# SAMD21_Pro_RF.net
KiCad netlist of a schematic drawn in EAGLE
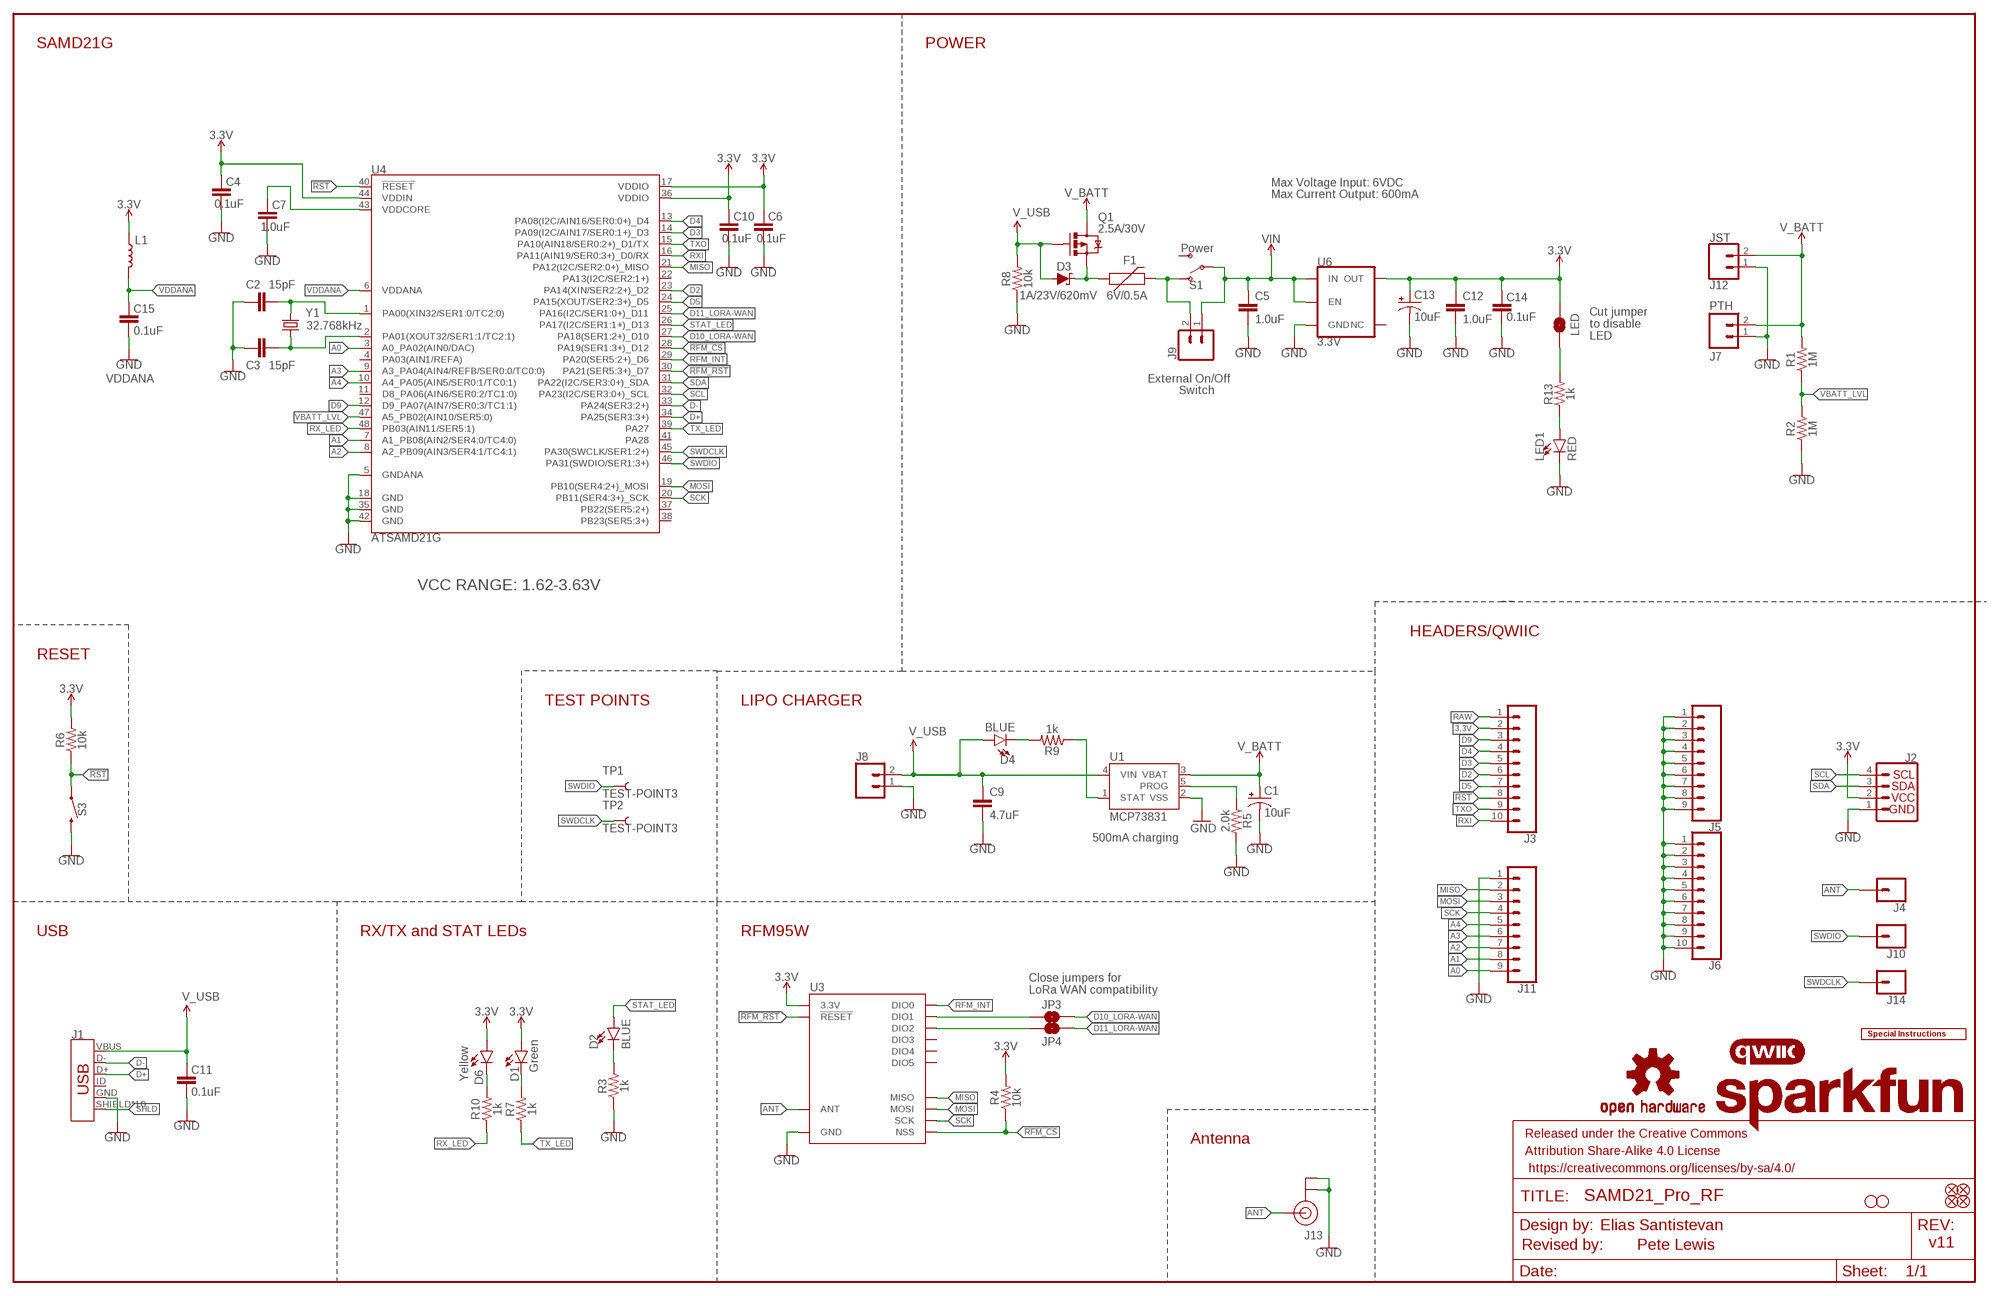
[diagram p0: schematic, sheet 1]

(export (version "E")
  (design (tool "Eeschema 10.0.6"))
  (components
    (comp (ref "C1")
      (value "10uF")
      (footprint "eagle-import:EIA3216")
      (libsource (lib "eagle-import") (part "10UF-POLAR-EIA3216-16V-10%(TANT)"))
    )
    (comp (ref "C2")
      (value "15pF")
      (footprint "eagle-import:0603")
      (libsource (lib "eagle-import") (part "15PF-0603-50V-5%"))
    )
    (comp (ref "C3")
      (value "15pF")
      (footprint "eagle-import:0603")
      (libsource (lib "eagle-import") (part "15PF-0603-50V-5%"))
    )
    (comp (ref "C4")
      (value "0.1uF")
      (footprint "eagle-import:0603")
      (libsource (lib "eagle-import") (part "0.1UF-0603-25V-(+80/-20%)"))
    )
    (comp (ref "C5")
      (value "1.0uF")
      (footprint "eagle-import:0603")
      (libsource (lib "eagle-import") (part "1.0UF-0603-16V-10%"))
    )
    (comp (ref "C6")
      (value "0.1uF")
      (footprint "eagle-import:0603")
      (libsource (lib "eagle-import") (part "0.1UF-0603-25V-(+80/-20%)"))
    )
    (comp (ref "C7")
      (value "1.0uF")
      (footprint "eagle-import:0603")
      (libsource (lib "eagle-import") (part "1.0UF-0603-16V-10%"))
    )
    (comp (ref "C9")
      (value "4.7uF")
      (footprint "eagle-import:0603")
      (libsource (lib "eagle-import") (part "4.7UF-0603-6.3V-(10%)"))
    )
    (comp (ref "C10")
      (value "0.1uF")
      (footprint "eagle-import:0603")
      (libsource (lib "eagle-import") (part "0.1UF-0603-25V-(+80/-20%)"))
    )
    (comp (ref "C11")
      (value "0.1uF")
      (footprint "eagle-import:0603")
      (libsource (lib "eagle-import") (part "0.1UF-0603-25V-(+80/-20%)"))
    )
    (comp (ref "C12")
      (value "1.0uF")
      (footprint "eagle-import:0603")
      (libsource (lib "eagle-import") (part "1.0UF-0603-16V-10%"))
    )
    (comp (ref "C13")
      (value "10uF")
      (footprint "eagle-import:EIA3216")
      (libsource (lib "eagle-import") (part "10UF-POLAR-EIA3216-16V-10%(TANT)"))
    )
    (comp (ref "C14")
      (value "0.1uF")
      (footprint "eagle-import:0603")
      (libsource (lib "eagle-import") (part "0.1UF-0603-25V-(+80/-20%)"))
    )
    (comp (ref "C15")
      (value "0.1uF")
      (footprint "eagle-import:0603")
      (libsource (lib "eagle-import") (part "0.1UF-0603-25V-(+80/-20%)"))
    )
    (comp (ref "D1")
      (value "Green")
      (footprint "eagle-import:LED-0603")
      (libsource (lib "eagle-import") (part "LED-GREEN0603"))
    )
    (comp (ref "D2")
      (value "BLUE")
      (footprint "eagle-import:LED-0603")
      (libsource (lib "eagle-import") (part "LED-BLUE0603"))
    )
    (comp (ref "D3")
      (value "1A/23V/620mV")
      (footprint "eagle-import:SOD-323")
      (libsource (lib "eagle-import") (part "DIODE-SCHOTTKY-BAT20J"))
    )
    (comp (ref "D4")
      (value "BLUE")
      (footprint "eagle-import:LED-0603")
      (libsource (lib "eagle-import") (part "LED-BLUE0603"))
    )
    (comp (ref "D6")
      (value "Yellow")
      (footprint "eagle-import:LED-0603")
      (libsource (lib "eagle-import") (part "LED-YELLOW0603"))
    )
    (comp (ref "F1")
      (value "6V/0.5A")
      (footprint "eagle-import:1206")
      (libsource (lib "eagle-import") (part "PPTC_HALF-AMP"))
    )
    (comp (ref "FD1")
      (value "FIDUCIAL1X2")
      (footprint "eagle-import:FIDUCIAL-1X2")
      (libsource (lib "eagle-import") (part "FIDUCIAL1X2"))
    )
    (comp (ref "FD2")
      (value "FIDUCIAL1X2")
      (footprint "eagle-import:FIDUCIAL-1X2")
      (libsource (lib "eagle-import") (part "FIDUCIAL1X2"))
    )
    (comp (ref "FD3")
      (value "FIDUCIAL1X2")
      (footprint "eagle-import:FIDUCIAL-1X2")
      (libsource (lib "eagle-import") (part "FIDUCIAL1X2"))
    )
    (comp (ref "FD4")
      (value "FIDUCIAL1X2")
      (footprint "eagle-import:FIDUCIAL-1X2")
      (libsource (lib "eagle-import") (part "FIDUCIAL1X2"))
    )
    (comp (ref "FRAME2")
      (value "FRAME-LEDGER")
      (footprint "eagle-import:CREATIVE_COMMONS")
      (libsource (lib "eagle-import") (part "FRAME-LEDGER"))
    )
    (comp (ref "H1")
      (value "STAND-OFFTIGHT")
      (footprint "eagle-import:STAND-OFF-TIGHT")
      (libsource (lib "eagle-import") (part "STAND-OFFTIGHT"))
    )
    (comp (ref "H2")
      (value "STAND-OFFTIGHT")
      (footprint "eagle-import:STAND-OFF-TIGHT")
      (libsource (lib "eagle-import") (part "STAND-OFFTIGHT"))
    )
    (comp (ref "J1")
      (value "USB_MICRO-B_HALF_PTH_MILL")
      (footprint "eagle-import:USB-MICROB-PTH-MILL")
      (libsource (lib "eagle-import") (part "USB_MICRO-B_HALF_PTH_MILL"))
    )
    (comp (ref "J2")
      (value "QWIIC_CONNECTORJS-1MM")
      (footprint "eagle-import:1X04_1MM_RA")
      (libsource (lib "eagle-import") (part "QWIIC_CONNECTORJS-1MM"))
    )
    (comp (ref "J3")
      (value "CONN_10NO_SILK_PTH_FEMALE")
      (footprint "eagle-import:1X10_NO_SILK")
      (libsource (lib "eagle-import") (part "CONN_10NO_SILK_PTH_FEMALE"))
    )
    (comp (ref "J4")
      (value "CONN_01PTH_NO_SILK_YES_STOP")
      (footprint "eagle-import:1X01_NO_SILK")
      (libsource (lib "eagle-import") (part "CONN_01PTH_NO_SILK_YES_STOP"))
    )
    (comp (ref "J5")
      (value "CONN_09NO_SILK")
      (footprint "eagle-import:1X09_NO_SILK")
      (libsource (lib "eagle-import") (part "CONN_09NO_SILK"))
    )
    (comp (ref "J6")
      (value "CONN_10NO_SILK_PTH_FEMALE")
      (footprint "eagle-import:1X10_NO_SILK")
      (libsource (lib "eagle-import") (part "CONN_10NO_SILK_PTH_FEMALE"))
    )
    (comp (ref "J7")
      (value "PTH")
      (footprint "eagle-import:1X02_NO_SILK")
      (libsource (lib "eagle-import") (part "CONN_021X02_NO_SILK"))
    )
    (comp (ref "J8")
      (value "CONN_021X02_NO_SILK")
      (footprint "eagle-import:1X02_NO_SILK")
      (libsource (lib "eagle-import") (part "CONN_021X02_NO_SILK"))
    )
    (comp (ref "J9")
      (value "External On/Off")
      (footprint "eagle-import:1X02_NO_SILK")
      (libsource (lib "eagle-import") (part "CONN_021X02_NO_SILK"))
    )
    (comp (ref "J10")
      (value "CONN_01PTH_NO_SILK_YES_STOP")
      (footprint "eagle-import:1X01_NO_SILK")
      (libsource (lib "eagle-import") (part "CONN_01PTH_NO_SILK_YES_STOP"))
    )
    (comp (ref "J11")
      (value "CONN_09NO_SILK")
      (footprint "eagle-import:1X09_NO_SILK")
      (libsource (lib "eagle-import") (part "CONN_09NO_SILK"))
    )
    (comp (ref "J12")
      (value "JST")
      (footprint "eagle-import:JST-2-SMD")
      (libsource (lib "eagle-import") (part "CONN_02-JST-2MM-SMT"))
    )
    (comp (ref "J13")
      (value "U.FL")
      (footprint "eagle-import:U.FL")
      (libsource (lib "eagle-import") (part "U.FL"))
    )
    (comp (ref "J14")
      (value "CONN_01PTH_NO_SILK_YES_STOP")
      (footprint "eagle-import:1X01_NO_SILK")
      (libsource (lib "eagle-import") (part "CONN_01PTH_NO_SILK_YES_STOP"))
    )
    (comp (ref "JP3")
      (value "JUMPER-SMT_2_NO_SILK")
      (footprint "eagle-import:SMT-JUMPER_2_NO_SILK")
      (libsource (lib "eagle-import") (part "JUMPER-SMT_2_NO_SILK"))
    )
    (comp (ref "JP4")
      (value "JUMPER-SMT_2_NO_SILK")
      (footprint "eagle-import:SMT-JUMPER_2_NO_SILK")
      (libsource (lib "eagle-import") (part "JUMPER-SMT_2_NO_SILK"))
    )
    (comp (ref "L1")
      (value "INDUCTORFB-30OHM")
      (footprint "eagle-import:0603")
      (libsource (lib "eagle-import") (part "INDUCTORFB-30OHM"))
    )
    (comp (ref "LED")
      (value "JUMPER-SMT_2_NC_TRACE_SILK")
      (footprint "eagle-import:SMT-JUMPER_2_NC_TRACE_SILK")
      (libsource (lib "eagle-import") (part "JUMPER-SMT_2_NC_TRACE_SILK"))
    )
    (comp (ref "LED1")
      (value "RED")
      (footprint "eagle-import:LED-0603")
      (libsource (lib "eagle-import") (part "LED-RED0603"))
    )
    (comp (ref "LOGO1")
      (value "OSHW-LOGOMINI")
      (footprint "eagle-import:OSHW-LOGO-MINI")
      (libsource (lib "eagle-import") (part "OSHW-LOGOMINI"))
    )
    (comp (ref "LOGO2")
      (value "SFE_LOGO_NAME.1_INCH")
      (footprint "eagle-import:SFE_LOGO_NAME_.1")
      (libsource (lib "eagle-import") (part "SFE_LOGO_NAME.1_INCH"))
    )
    (comp (ref "LOGO3")
      (value "QWIIC_LOGO_5MM")
      (footprint "eagle-import:QWIIC_5MM")
      (libsource (lib "eagle-import") (part "QWIIC_LOGO_5MM"))
    )
    (comp (ref "Q1")
      (value "2.5A/30V")
      (footprint "eagle-import:SOT23-3@1")
      (libsource (lib "eagle-import") (part "MOSFET-PCHANNELDMG2307L"))
    )
    (comp (ref "R1")
      (value "1M")
      (footprint "eagle-import:0603")
      (libsource (lib "eagle-import") (part "1MOHM-0603-1/4W-5%"))
    )
    (comp (ref "R2")
      (value "1M")
      (footprint "eagle-import:0603")
      (libsource (lib "eagle-import") (part "1MOHM-0603-1/4W-5%"))
    )
    (comp (ref "R3")
      (value "1k")
      (footprint "eagle-import:0603")
      (libsource (lib "eagle-import") (part "1KOHM-0603-1/10W-1%"))
    )
    (comp (ref "R4")
      (value "10k")
      (footprint "eagle-import:0603")
      (libsource (lib "eagle-import") (part "10KOHM-0603-1/10W-1%"))
    )
    (comp (ref "R5")
      (value "2.0k")
      (footprint "eagle-import:0603")
      (libsource (lib "eagle-import") (part "2.0KOHM-0603-1/10W-5%"))
    )
    (comp (ref "R6")
      (value "10k")
      (footprint "eagle-import:0603")
      (libsource (lib "eagle-import") (part "10KOHM-0603-1/10W-1%"))
    )
    (comp (ref "R7")
      (value "1k")
      (footprint "eagle-import:0603")
      (libsource (lib "eagle-import") (part "1KOHM-0603-1/10W-1%"))
    )
    (comp (ref "R8")
      (value "10k")
      (footprint "eagle-import:0603")
      (libsource (lib "eagle-import") (part "10KOHM-0603-1/10W-1%"))
    )
    (comp (ref "R9")
      (value "1k")
      (footprint "eagle-import:0603")
      (libsource (lib "eagle-import") (part "1KOHM-0603-1/10W-1%"))
    )
    (comp (ref "R10")
      (value "1k")
      (footprint "eagle-import:0603")
      (libsource (lib "eagle-import") (part "1KOHM-0603-1/10W-1%"))
    )
    (comp (ref "R13")
      (value "1k")
      (footprint "eagle-import:0603")
      (libsource (lib "eagle-import") (part "1KOHM-0603-1/10W-1%"))
    )
    (comp (ref "S1")
      (value "Power")
      (footprint "eagle-import:SWITCH_SPST_SMD_A")
      (libsource (lib "eagle-import") (part "SWITCH-SPDT-SMD-RIGHT-ANGLE"))
    )
    (comp (ref "S3")
      (value "MOMENTARY-SWITCH-SPST-SMD-RIGHT-ANGLE")
      (footprint "eagle-import:TACTILE_SWITCH_SMD_RIGHT_ANGLE")
      (libsource (lib "eagle-import") (part "MOMENTARY-SWITCH-SPST-SMD-RIGHT-ANGLE"))
    )
    (comp (ref "TP1")
      (value "TEST-POINT3")
      (footprint "eagle-import:PAD.03X.03")
      (libsource (lib "eagle-import") (part "TEST-POINT3"))
    )
    (comp (ref "TP2")
      (value "TEST-POINT3")
      (footprint "eagle-import:PAD.03X.03")
      (libsource (lib "eagle-import") (part "TEST-POINT3"))
    )
    (comp (ref "U$26")
      (value "SPECIAL_INSTRUCTIONS-ORDERING")
      (footprint "eagle-import:ORDERING_INSTRUCTIONS")
      (libsource (lib "eagle-import") (part "SPECIAL_INSTRUCTIONS-ORDERING"))
    )
    (comp (ref "U1")
      (value "MCP73831")
      (footprint "eagle-import:SOT23-5")
      (libsource (lib "eagle-import") (part "MCP73831"))
    )
    (comp (ref "U3")
      (value "RFM95W")
      (footprint "eagle-import:RFM95_96_97_98W")
      (libsource (lib "eagle-import") (part "RFM95W"))
    )
    (comp (ref "U4")
      (value "ATSAMD21G")
      (footprint "eagle-import:QFN-48_NO_EXPOSED_PAD")
      (libsource (lib "eagle-import") (part "ATSAMD21G"))
    )
    (comp (ref "U6")
      (value "3.3V")
      (footprint "eagle-import:SOT23-5")
      (libsource (lib "eagle-import") (part "V_REG_AP2112K-3.3V"))
    )
    (comp (ref "Y1")
      (value "32.768kHz")
      (footprint "eagle-import:CRYSTAL-SMD-3.2X1.5MM")
      (libsource (lib "eagle-import") (part "CRYSTAL-32.768KHZSMD-3.2X1.5"))
    )
  )
  (nets
    (net (code "1") (name "/~{RFM_CS}") (class "Default")
      (node (ref "R4") (pin "1") (pinfunction "1_1") (pintype "passive"))
      (node (ref "U3") (pin "NSS") (pinfunction "NSS_NSS") (pintype "bidirectional"))
      (node (ref "U4") (pin "28") (pinfunction "PA19(SER1:3+)_D12_28") (pintype "bidirectional"))
    )
    (net (code "2") (name "/~{RFM_RST}") (class "Default")
      (node (ref "U3") (pin "!RESET") (pinfunction "~{RESET}_!RESET") (pintype "bidirectional"))
      (node (ref "U4") (pin "30") (pinfunction "PA21(SER5:3+)_D7_30") (pintype "bidirectional"))
    )
    (net (code "3") (name "/~{RST}") (class "Default")
      (node (ref "J3") (pin "8") (pinfunction "8_8") (pintype "passive"))
      (node (ref "R6") (pin "1") (pinfunction "1_1") (pintype "passive"))
      (node (ref "S3") (pin "1") (pinfunction "1_1") (pintype "passive"))
      (node (ref "U4") (pin "40") (pinfunction "~{RESET}_40") (pintype "bidirectional"))
    )
    (net (code "4") (name "3.3V") (class "Default")
      (node (ref "C10") (pin "2") (pinfunction "2_2") (pintype "passive"))
      (node (ref "C12") (pin "1") (pinfunction "1_1") (pintype "passive"))
      (node (ref "C13") (pin "+") (pinfunction "+_+") (pintype "passive"))
      (node (ref "C14") (pin "2") (pinfunction "2_2") (pintype "passive"))
      (node (ref "C4") (pin "2") (pinfunction "2_2") (pintype "passive"))
      (node (ref "C6") (pin "2") (pinfunction "2_2") (pintype "passive"))
      (node (ref "D1") (pin "A") (pinfunction "A_A") (pintype "passive"))
      (node (ref "D6") (pin "A") (pinfunction "A_A") (pintype "passive"))
      (node (ref "J2") (pin "2") (pinfunction "2_2") (pintype "power_in"))
      (node (ref "J3") (pin "2") (pinfunction "2_2") (pintype "passive"))
      (node (ref "L1") (pin "1") (pinfunction "1_1") (pintype "passive"))
      (node (ref "LED") (pin "1") (pinfunction "1_1") (pintype "passive"))
      (node (ref "R4") (pin "2") (pinfunction "2_2") (pintype "passive"))
      (node (ref "R6") (pin "2") (pinfunction "2_2") (pintype "passive"))
      (node (ref "U3") (pin "3.3V") (pinfunction "3.3V_3.3V") (pintype "bidirectional"))
      (node (ref "U4") (pin "17") (pinfunction "VDDIO_17") (pintype "bidirectional"))
      (node (ref "U4") (pin "36") (pinfunction "VDDIO_36") (pintype "bidirectional"))
      (node (ref "U4") (pin "44") (pinfunction "VDDIN_44") (pintype "bidirectional"))
      (node (ref "U6") (pin "5") (pinfunction "OUT_5") (pintype "passive"))
    )
    (net (code "5") (name "A0") (class "Default")
      (node (ref "J11") (pin "9") (pinfunction "9_9") (pintype "passive"))
      (node (ref "U4") (pin "3") (pinfunction "A0_PA02(AIN0/DAC)_3") (pintype "bidirectional"))
    )
    (net (code "6") (name "A1") (class "Default")
      (node (ref "J11") (pin "8") (pinfunction "8_8") (pintype "passive"))
      (node (ref "U4") (pin "7") (pinfunction "A1_PB08(AIN2/SER4:0/TC4:0)_7") (pintype "bidirectional"))
    )
    (net (code "7") (name "A2") (class "Default")
      (node (ref "J11") (pin "7") (pinfunction "7_7") (pintype "passive"))
      (node (ref "U4") (pin "8") (pinfunction "A2_PB09(AIN3/SER4:1/TC4:1)_8") (pintype "bidirectional"))
    )
    (net (code "8") (name "A3") (class "Default")
      (node (ref "J11") (pin "6") (pinfunction "6_6") (pintype "passive"))
      (node (ref "U4") (pin "9") (pinfunction "A3_PA04(AIN4/REFB/SER0:0/TC0:0)_9") (pintype "bidirectional"))
    )
    (net (code "9") (name "A4") (class "Default")
      (node (ref "J11") (pin "5") (pinfunction "5_5") (pintype "passive"))
      (node (ref "U4") (pin "10") (pinfunction "A4_PA05(AIN5/SER0:1/TC0:1)_10") (pintype "bidirectional"))
    )
    (net (code "10") (name "ANT") (class "Default")
      (node (ref "J13") (pin "FEED") (pinfunction "SIGNAL_FEED") (pintype "bidirectional"))
      (node (ref "J4") (pin "1") (pinfunction "1_1") (pintype "passive"))
      (node (ref "U3") (pin "ANT") (pinfunction "ANT_ANT") (pintype "bidirectional"))
    )
    (net (code "11") (name "D+") (class "Default")
      (node (ref "J1") (pin "D+") (pinfunction "D+_D+") (pintype "bidirectional"))
      (node (ref "U4") (pin "34") (pinfunction "PA25(SER3:3+)_34") (pintype "bidirectional"))
    )
    (net (code "12") (name "D-") (class "Default")
      (node (ref "J1") (pin "D-") (pinfunction "D-_D-") (pintype "bidirectional"))
      (node (ref "U4") (pin "33") (pinfunction "PA24(SER3:2+)_33") (pintype "bidirectional"))
    )
    (net (code "13") (name "D2") (class "Default")
      (node (ref "J3") (pin "6") (pinfunction "6_6") (pintype "passive"))
      (node (ref "U4") (pin "23") (pinfunction "PA14(XIN/SER2:2+)_D2_23") (pintype "bidirectional"))
    )
    (net (code "14") (name "D3") (class "Default")
      (node (ref "J3") (pin "5") (pinfunction "5_5") (pintype "passive"))
      (node (ref "U4") (pin "14") (pinfunction "PA09(I2C/AIN17/SER0:1+)_D3_14") (pintype "bidirectional"))
    )
    (net (code "15") (name "D4") (class "Default")
      (node (ref "J3") (pin "4") (pinfunction "4_4") (pintype "passive"))
      (node (ref "U4") (pin "13") (pinfunction "PA08(I2C/AIN16/SER0:0+)_D4_13") (pintype "bidirectional"))
    )
    (net (code "16") (name "D5") (class "Default")
      (node (ref "J3") (pin "7") (pinfunction "7_7") (pintype "passive"))
      (node (ref "U4") (pin "24") (pinfunction "PA15(XOUT/SER2:3+)_D5_24") (pintype "bidirectional"))
    )
    (net (code "17") (name "D9") (class "Default")
      (node (ref "J3") (pin "3") (pinfunction "3_3") (pintype "passive"))
      (node (ref "U4") (pin "12") (pinfunction "D9_PA07(AIN7/SER0:3/TC1:1)_12") (pintype "bidirectional"))
    )
    (net (code "18") (name "D10_LORA-WAN") (class "Default")
      (node (ref "JP3") (pin "2") (pinfunction "2_2") (pintype "passive"))
      (node (ref "U4") (pin "27") (pinfunction "PA18(SER1:2+)_D10_27") (pintype "bidirectional"))
    )
    (net (code "19") (name "D11_LORA-WAN") (class "Default")
      (node (ref "JP4") (pin "2") (pinfunction "2_2") (pintype "passive"))
      (node (ref "U4") (pin "25") (pinfunction "PA16(I2C/SER1:0+)_D11_25") (pintype "bidirectional"))
    )
    (net (code "20") (name "GND") (class "Default")
      (node (ref "C1") (pin "-") (pinfunction "-_-") (pintype "passive"))
      (node (ref "C10") (pin "1") (pinfunction "1_1") (pintype "passive"))
      (node (ref "C11") (pin "1") (pinfunction "1_1") (pintype "passive"))
      (node (ref "C12") (pin "2") (pinfunction "2_2") (pintype "passive"))
      (node (ref "C13") (pin "-") (pinfunction "-_-") (pintype "passive"))
      (node (ref "C14") (pin "1") (pinfunction "1_1") (pintype "passive"))
      (node (ref "C15") (pin "1") (pinfunction "1_1") (pintype "passive"))
      (node (ref "C2") (pin "1") (pinfunction "1_1") (pintype "passive"))
      (node (ref "C3") (pin "1") (pinfunction "1_1") (pintype "passive"))
      (node (ref "C4") (pin "1") (pinfunction "1_1") (pintype "passive"))
      (node (ref "C5") (pin "2") (pinfunction "2_2") (pintype "passive"))
      (node (ref "C6") (pin "1") (pinfunction "1_1") (pintype "passive"))
      (node (ref "C7") (pin "1") (pinfunction "1_1") (pintype "passive"))
      (node (ref "C9") (pin "2") (pinfunction "2_2") (pintype "passive"))
      (node (ref "J1") (pin "GND") (pinfunction "GND_GND") (pintype "power_in"))
      (node (ref "J11") (pin "1") (pinfunction "1_1") (pintype "passive"))
      (node (ref "J12") (pin "1") (pinfunction "2_1") (pintype "passive"))
      (node (ref "J13") (pin "1") (pinfunction "GND_1") (pintype "bidirectional"))
      (node (ref "J13") (pin "2") (pinfunction "GND_2") (pintype "bidirectional"))
      (node (ref "J2") (pin "1") (pinfunction "1_1") (pintype "power_in"))
      (node (ref "J5") (pin "1") (pinfunction "1_1") (pintype "passive"))
      (node (ref "J5") (pin "2") (pinfunction "2_2") (pintype "passive"))
      (node (ref "J5") (pin "3") (pinfunction "3_3") (pintype "passive"))
      (node (ref "J5") (pin "4") (pinfunction "4_4") (pintype "passive"))
      (node (ref "J5") (pin "5") (pinfunction "5_5") (pintype "passive"))
      (node (ref "J5") (pin "6") (pinfunction "6_6") (pintype "passive"))
      (node (ref "J5") (pin "7") (pinfunction "7_7") (pintype "passive"))
      (node (ref "J5") (pin "8") (pinfunction "8_8") (pintype "passive"))
      (node (ref "J5") (pin "9") (pinfunction "9_9") (pintype "passive"))
      (node (ref "J6") (pin "1") (pinfunction "1_1") (pintype "passive"))
      (node (ref "J6") (pin "10") (pinfunction "10_10") (pintype "passive"))
      (node (ref "J6") (pin "2") (pinfunction "2_2") (pintype "passive"))
      (node (ref "J6") (pin "3") (pinfunction "3_3") (pintype "passive"))
      (node (ref "J6") (pin "4") (pinfunction "4_4") (pintype "passive"))
      (node (ref "J6") (pin "5") (pinfunction "5_5") (pintype "passive"))
      (node (ref "J6") (pin "6") (pinfunction "6_6") (pintype "passive"))
      (node (ref "J6") (pin "7") (pinfunction "7_7") (pintype "passive"))
      (node (ref "J6") (pin "8") (pinfunction "8_8") (pintype "passive"))
      (node (ref "J6") (pin "9") (pinfunction "9_9") (pintype "passive"))
      (node (ref "J7") (pin "1") (pinfunction "1_1") (pintype "passive"))
      (node (ref "J8") (pin "1") (pinfunction "1_1") (pintype "passive"))
      (node (ref "LED1") (pin "C") (pinfunction "C_C") (pintype "passive"))
      (node (ref "R2") (pin "1") (pinfunction "1_1") (pintype "passive"))
      (node (ref "R3") (pin "1") (pinfunction "1_1") (pintype "passive"))
      (node (ref "R5") (pin "2") (pinfunction "2_2") (pintype "passive"))
      (node (ref "R8") (pin "1") (pinfunction "1_1") (pintype "passive"))
      (node (ref "S3") (pin "2") (pinfunction "2_2") (pintype "passive"))
      (node (ref "U1") (pin "2") (pinfunction "VSS_2") (pintype "power_in"))
      (node (ref "U3") (pin "GND@1") (pinfunction "GND_GND@1") (pintype "bidirectional"))
      (node (ref "U3") (pin "GND@2") (pinfunction "GND_GND@2") (pintype "bidirectional"))
      (node (ref "U3") (pin "GND@3") (pinfunction "GND_GND@3") (pintype "bidirectional"))
      (node (ref "U4") (pin "18") (pinfunction "GND_18") (pintype "bidirectional"))
      (node (ref "U4") (pin "35") (pinfunction "GND_35") (pintype "bidirectional"))
      (node (ref "U4") (pin "42") (pinfunction "GND_42") (pintype "bidirectional"))
      (node (ref "U4") (pin "5") (pinfunction "GNDANA_5") (pintype "bidirectional"))
      (node (ref "U6") (pin "2") (pinfunction "GND_2") (pintype "input"))
    )
    (net (code "21") (name "MISO") (class "Default")
      (node (ref "J11") (pin "2") (pinfunction "2_2") (pintype "passive"))
      (node (ref "U3") (pin "MISO") (pinfunction "MISO_MISO") (pintype "bidirectional"))
      (node (ref "U4") (pin "21") (pinfunction "PA12(I2C/SER2:0+)_MISO_21") (pintype "bidirectional"))
    )
    (net (code "22") (name "MOSI") (class "Default")
      (node (ref "J11") (pin "3") (pinfunction "3_3") (pintype "passive"))
      (node (ref "U3") (pin "MOSI") (pinfunction "MOSI_MOSI") (pintype "bidirectional"))
      (node (ref "U4") (pin "19") (pinfunction "PB10(SER4:2+)_MOSI_19") (pintype "bidirectional"))
    )
    (net (code "23") (name "Net-(D1-PadC)") (class "Default")
      (node (ref "D1") (pin "C") (pinfunction "C_C") (pintype "passive"))
      (node (ref "R7") (pin "2") (pinfunction "2_2") (pintype "passive"))
    )
    (net (code "24") (name "Net-(D2-PadC)") (class "Default")
      (node (ref "D2") (pin "C") (pinfunction "C_C") (pintype "passive"))
      (node (ref "R3") (pin "2") (pinfunction "2_2") (pintype "passive"))
    )
    (net (code "25") (name "Net-(D4-PadC)") (class "Default")
      (node (ref "D4") (pin "C") (pinfunction "C_C") (pintype "passive"))
      (node (ref "R9") (pin "2") (pinfunction "2_2") (pintype "passive"))
    )
    (net (code "26") (name "Net-(D6-PadC)") (class "Default")
      (node (ref "D6") (pin "C") (pinfunction "C_C") (pintype "passive"))
      (node (ref "R10") (pin "2") (pinfunction "2_2") (pintype "passive"))
    )
    (net (code "27") (name "Net-(JP3-Pad1)") (class "Default")
      (node (ref "JP3") (pin "1") (pinfunction "1_1") (pintype "passive"))
      (node (ref "U3") (pin "DIO1") (pinfunction "DIO1_DIO1") (pintype "bidirectional"))
    )
    (net (code "28") (name "Net-(JP4-Pad1)") (class "Default")
      (node (ref "JP4") (pin "1") (pinfunction "1_1") (pintype "passive"))
      (node (ref "U3") (pin "DIO2") (pinfunction "DIO2_DIO2") (pintype "bidirectional"))
    )
    (net (code "29") (name "Net-(LED-Pad2)") (class "Default")
      (node (ref "LED") (pin "2") (pinfunction "2_2") (pintype "passive"))
      (node (ref "R13") (pin "2") (pinfunction "2_2") (pintype "passive"))
    )
    (net (code "30") (name "Net-(LED1-PadA)") (class "Default")
      (node (ref "LED1") (pin "A") (pinfunction "A_A") (pintype "passive"))
      (node (ref "R13") (pin "1") (pinfunction "1_1") (pintype "passive"))
    )
    (net (code "31") (name "Net-(S1-O)") (class "Default")
      (node (ref "F1") (pin "2") (pinfunction "2_2") (pintype "bidirectional"))
      (node (ref "J9") (pin "2") (pinfunction "2_2") (pintype "passive"))
      (node (ref "S1") (pin "1") (pinfunction "O_1") (pintype "passive"))
    )
    (net (code "32") (name "Net-(U1-PROG)") (class "Default")
      (node (ref "R5") (pin "1") (pinfunction "1_1") (pintype "passive"))
      (node (ref "U1") (pin "5") (pinfunction "PROG_5") (pintype "input"))
    )
    (net (code "33") (name "Net-(U1-STAT)") (class "Default")
      (node (ref "R9") (pin "1") (pinfunction "1_1") (pintype "passive"))
      (node (ref "U1") (pin "1") (pinfunction "STAT_1") (pintype "output"))
    )
    (net (code "34") (name "Net-(U4-PA00(XIN32{slash}SER1:0{slash}TC2:0))") (class "Default")
      (node (ref "C2") (pin "2") (pinfunction "2_2") (pintype "passive"))
      (node (ref "U4") (pin "1") (pinfunction "PA00(XIN32/SER1:0/TC2:0)_1") (pintype "bidirectional"))
      (node (ref "Y1") (pin "P$2") (pinfunction "2_P$2") (pintype "passive"))
    )
    (net (code "35") (name "Net-(U4-PA01(XOUT32{slash}SER1:1{slash}TC2:1))") (class "Default")
      (node (ref "C3") (pin "2") (pinfunction "2_2") (pintype "passive"))
      (node (ref "U4") (pin "2") (pinfunction "PA01(XOUT32/SER1:1/TC2:1)_2") (pintype "bidirectional"))
      (node (ref "Y1") (pin "P$1") (pinfunction "1_P$1") (pintype "passive"))
    )
    (net (code "36") (name "Net-(U4-VDDCORE)") (class "Default")
      (node (ref "C7") (pin "2") (pinfunction "2_2") (pintype "passive"))
      (node (ref "U4") (pin "43") (pinfunction "VDDCORE_43") (pintype "bidirectional"))
    )
    (net (code "37") (name "RAW") (class "Default")
      (node (ref "D3") (pin "C") (pinfunction "C_C") (pintype "passive"))
      (node (ref "F1") (pin "1") (pinfunction "1_1") (pintype "bidirectional"))
      (node (ref "J3") (pin "1") (pinfunction "1_1") (pintype "passive"))
      (node (ref "Q1") (pin "2") (pinfunction "S_2") (pintype "passive"))
    )
    (net (code "38") (name "RFM_INT") (class "Default")
      (node (ref "U3") (pin "DIO0") (pinfunction "DIO0_DIO0") (pintype "bidirectional"))
      (node (ref "U4") (pin "29") (pinfunction "PA20(SER5:2+)_D6_29") (pintype "bidirectional"))
    )
    (net (code "39") (name "RXI") (class "Default")
      (node (ref "J3") (pin "10") (pinfunction "10_10") (pintype "passive"))
      (node (ref "U4") (pin "16") (pinfunction "PA11(AIN19/SER0:3+)_D0/RX_16") (pintype "bidirectional"))
    )
    (net (code "40") (name "RX_LED") (class "Default")
      (node (ref "R10") (pin "1") (pinfunction "1_1") (pintype "passive"))
      (node (ref "U4") (pin "48") (pinfunction "PB03(AIN11/SER5:1)_48") (pintype "bidirectional"))
    )
    (net (code "41") (name "SCK") (class "Default")
      (node (ref "J11") (pin "4") (pinfunction "4_4") (pintype "passive"))
      (node (ref "U3") (pin "SCK") (pinfunction "SCK_SCK") (pintype "bidirectional"))
      (node (ref "U4") (pin "20") (pinfunction "PB11(SER4:3+)_SCK_20") (pintype "bidirectional"))
    )
    (net (code "42") (name "SCL") (class "Default")
      (node (ref "J2") (pin "4") (pinfunction "4_4") (pintype "passive"))
      (node (ref "U4") (pin "32") (pinfunction "PA23(I2C/SER3:0+)_SCL_32") (pintype "bidirectional"))
    )
    (net (code "43") (name "SDA") (class "Default")
      (node (ref "J2") (pin "3") (pinfunction "3_3") (pintype "passive"))
      (node (ref "U4") (pin "31") (pinfunction "PA22(I2C/SER3:0+)_SDA_31") (pintype "bidirectional"))
    )
    (net (code "44") (name "SHLD") (class "Default")
      (node (ref "J1") (pin "SHIELD") (pinfunction "SHIELD_SHIELD") (pintype "bidirectional"))
      (node (ref "J1") (pin "SHIELD10") (pinfunction "SHIELD_SHIELD10") (pintype "bidirectional"))
      (node (ref "J1") (pin "SHIELD2") (pinfunction "SHIELD_SHIELD2") (pintype "bidirectional"))
      (node (ref "J1") (pin "SHIELD3") (pinfunction "SHIELD_SHIELD3") (pintype "bidirectional"))
      (node (ref "J1") (pin "SHIELD4") (pinfunction "SHIELD_SHIELD4") (pintype "bidirectional"))
      (node (ref "J1") (pin "SHIELD5") (pinfunction "SHIELD_SHIELD5") (pintype "bidirectional"))
      (node (ref "J1") (pin "SHIELD6") (pinfunction "SHIELD_SHIELD6") (pintype "bidirectional"))
      (node (ref "J1") (pin "SHIELD7") (pinfunction "SHIELD_SHIELD7") (pintype "bidirectional"))
      (node (ref "J1") (pin "SHIELD8") (pinfunction "SHIELD_SHIELD8") (pintype "bidirectional"))
      (node (ref "J1") (pin "SHIELD9") (pinfunction "SHIELD_SHIELD9") (pintype "bidirectional"))
    )
    (net (code "45") (name "STAT_LED") (class "Default")
      (node (ref "D2") (pin "A") (pinfunction "A_A") (pintype "passive"))
      (node (ref "U4") (pin "26") (pinfunction "PA17(I2C/SER1:1+)_D13_26") (pintype "bidirectional"))
    )
    (net (code "46") (name "SWDCLK") (class "Default")
      (node (ref "J14") (pin "1") (pinfunction "1_1") (pintype "passive"))
      (node (ref "TP2") (pin "P$1") (pinfunction "1_P$1") (pintype "bidirectional"))
      (node (ref "U4") (pin "45") (pinfunction "PA30(SWCLK/SER1:2+)_45") (pintype "bidirectional"))
    )
    (net (code "47") (name "SWDIO") (class "Default")
      (node (ref "J10") (pin "1") (pinfunction "1_1") (pintype "passive"))
      (node (ref "TP1") (pin "P$1") (pinfunction "1_P$1") (pintype "bidirectional"))
      (node (ref "U4") (pin "46") (pinfunction "PA31(SWDIO/SER1:3+)_46") (pintype "bidirectional"))
    )
    (net (code "48") (name "TXO") (class "Default")
      (node (ref "J3") (pin "9") (pinfunction "9_9") (pintype "passive"))
      (node (ref "U4") (pin "15") (pinfunction "PA10(AIN18/SER0:2+)_D1/TX_15") (pintype "bidirectional"))
    )
    (net (code "49") (name "TX_LED") (class "Default")
      (node (ref "R7") (pin "1") (pinfunction "1_1") (pintype "passive"))
      (node (ref "U4") (pin "39") (pinfunction "PA27_39") (pintype "bidirectional"))
    )
    (net (code "50") (name "VBATT_LVL") (class "Default")
      (node (ref "R1") (pin "1") (pinfunction "1_1") (pintype "passive"))
      (node (ref "R2") (pin "2") (pinfunction "2_2") (pintype "passive"))
      (node (ref "U4") (pin "47") (pinfunction "A5_PB02(AIN10/SER5:0)_47") (pintype "bidirectional"))
    )
    (net (code "51") (name "VDDANA") (class "Default")
      (node (ref "C15") (pin "2") (pinfunction "2_2") (pintype "passive"))
      (node (ref "L1") (pin "2") (pinfunction "2_2") (pintype "passive"))
      (node (ref "U4") (pin "6") (pinfunction "VDDANA_6") (pintype "bidirectional"))
    )
    (net (code "52") (name "VIN") (class "Default")
      (node (ref "C5") (pin "1") (pinfunction "1_1") (pintype "passive"))
      (node (ref "J9") (pin "1") (pinfunction "1_1") (pintype "passive"))
      (node (ref "S1") (pin "2") (pinfunction "P_2") (pintype "passive"))
      (node (ref "U6") (pin "1") (pinfunction "IN_1") (pintype "input"))
      (node (ref "U6") (pin "3") (pinfunction "EN_3") (pintype "input"))
    )
    (net (code "53") (name "V_BATT") (class "Default")
      (node (ref "C1") (pin "+") (pinfunction "+_+") (pintype "passive"))
      (node (ref "J12") (pin "2") (pinfunction "1_2") (pintype "passive"))
      (node (ref "J7") (pin "2") (pinfunction "2_2") (pintype "passive"))
      (node (ref "Q1") (pin "3") (pinfunction "D_3") (pintype "passive"))
      (node (ref "R1") (pin "2") (pinfunction "2_2") (pintype "passive"))
      (node (ref "U1") (pin "3") (pinfunction "VBAT_3") (pintype "power_in"))
    )
    (net (code "54") (name "V_USB") (class "Default")
      (node (ref "C11") (pin "2") (pinfunction "2_2") (pintype "passive"))
      (node (ref "C9") (pin "1") (pinfunction "1_1") (pintype "passive"))
      (node (ref "D3") (pin "A") (pinfunction "A_A") (pintype "passive"))
      (node (ref "D4") (pin "A") (pinfunction "A_A") (pintype "passive"))
      (node (ref "J1") (pin "VBUS") (pinfunction "VBUS_VBUS") (pintype "power_in"))
      (node (ref "J8") (pin "2") (pinfunction "2_2") (pintype "passive"))
      (node (ref "Q1") (pin "1") (pinfunction "G_1") (pintype "passive"))
      (node (ref "R8") (pin "2") (pinfunction "2_2") (pintype "passive"))
      (node (ref "U1") (pin "4") (pinfunction "VIN_4") (pintype "power_in"))
    )
    (net (code "55") (name "unconnected-(J1-PadID)") (class "Default")
      (node (ref "J1") (pin "ID") (pinfunction "ID_ID") (pintype "bidirectional"))
    )
    (net (code "56") (name "unconnected-(S1-S-Pad3)") (class "Default")
      (node (ref "S1") (pin "3") (pinfunction "S_3") (pintype "passive"))
    )
    (net (code "57") (name "unconnected-(U3-PadDIO3)") (class "Default")
      (node (ref "U3") (pin "DIO3") (pinfunction "DIO3_DIO3") (pintype "bidirectional"))
    )
    (net (code "58") (name "unconnected-(U3-PadDIO4)") (class "Default")
      (node (ref "U3") (pin "DIO4") (pinfunction "DIO4_DIO4") (pintype "bidirectional"))
    )
    (net (code "59") (name "unconnected-(U3-PadDIO5)") (class "Default")
      (node (ref "U3") (pin "DIO5") (pinfunction "DIO5_DIO5") (pintype "bidirectional"))
    )
    (net (code "60") (name "unconnected-(U4-D8_PA06(AIN6{slash}SER0:2{slash}TC1:0)-Pad11)") (class "Default")
      (node (ref "U4") (pin "11") (pinfunction "D8_PA06(AIN6/SER0:2/TC1:0)_11") (pintype "bidirectional"))
    )
    (net (code "61") (name "unconnected-(U4-PA03(AIN1{slash}REFA)-Pad4)") (class "Default")
      (node (ref "U4") (pin "4") (pinfunction "PA03(AIN1/REFA)_4") (pintype "bidirectional"))
    )
    (net (code "62") (name "unconnected-(U4-PA13(I2C{slash}SER2:1+)-Pad22)") (class "Default")
      (node (ref "U4") (pin "22") (pinfunction "PA13(I2C/SER2:1+)_22") (pintype "bidirectional"))
    )
    (net (code "63") (name "unconnected-(U4-PA28-Pad41)") (class "Default")
      (node (ref "U4") (pin "41") (pinfunction "PA28_41") (pintype "bidirectional"))
    )
    (net (code "64") (name "unconnected-(U4-PB22(SER5:2+)-Pad37)") (class "Default")
      (node (ref "U4") (pin "37") (pinfunction "PB22(SER5:2+)_37") (pintype "bidirectional"))
    )
    (net (code "65") (name "unconnected-(U4-PB23(SER5:3+)-Pad38)") (class "Default")
      (node (ref "U4") (pin "38") (pinfunction "PB23(SER5:3+)_38") (pintype "bidirectional"))
    )
    (net (code "66") (name "unconnected-(U6-NC-Pad4)") (class "Default")
      (node (ref "U6") (pin "4") (pinfunction "NC_4") (pintype "no_connect"))
    )
  )
)
